# Kasli-SOC_bank13.net
KiCad netlist of a schematic drawn in Altium Designer
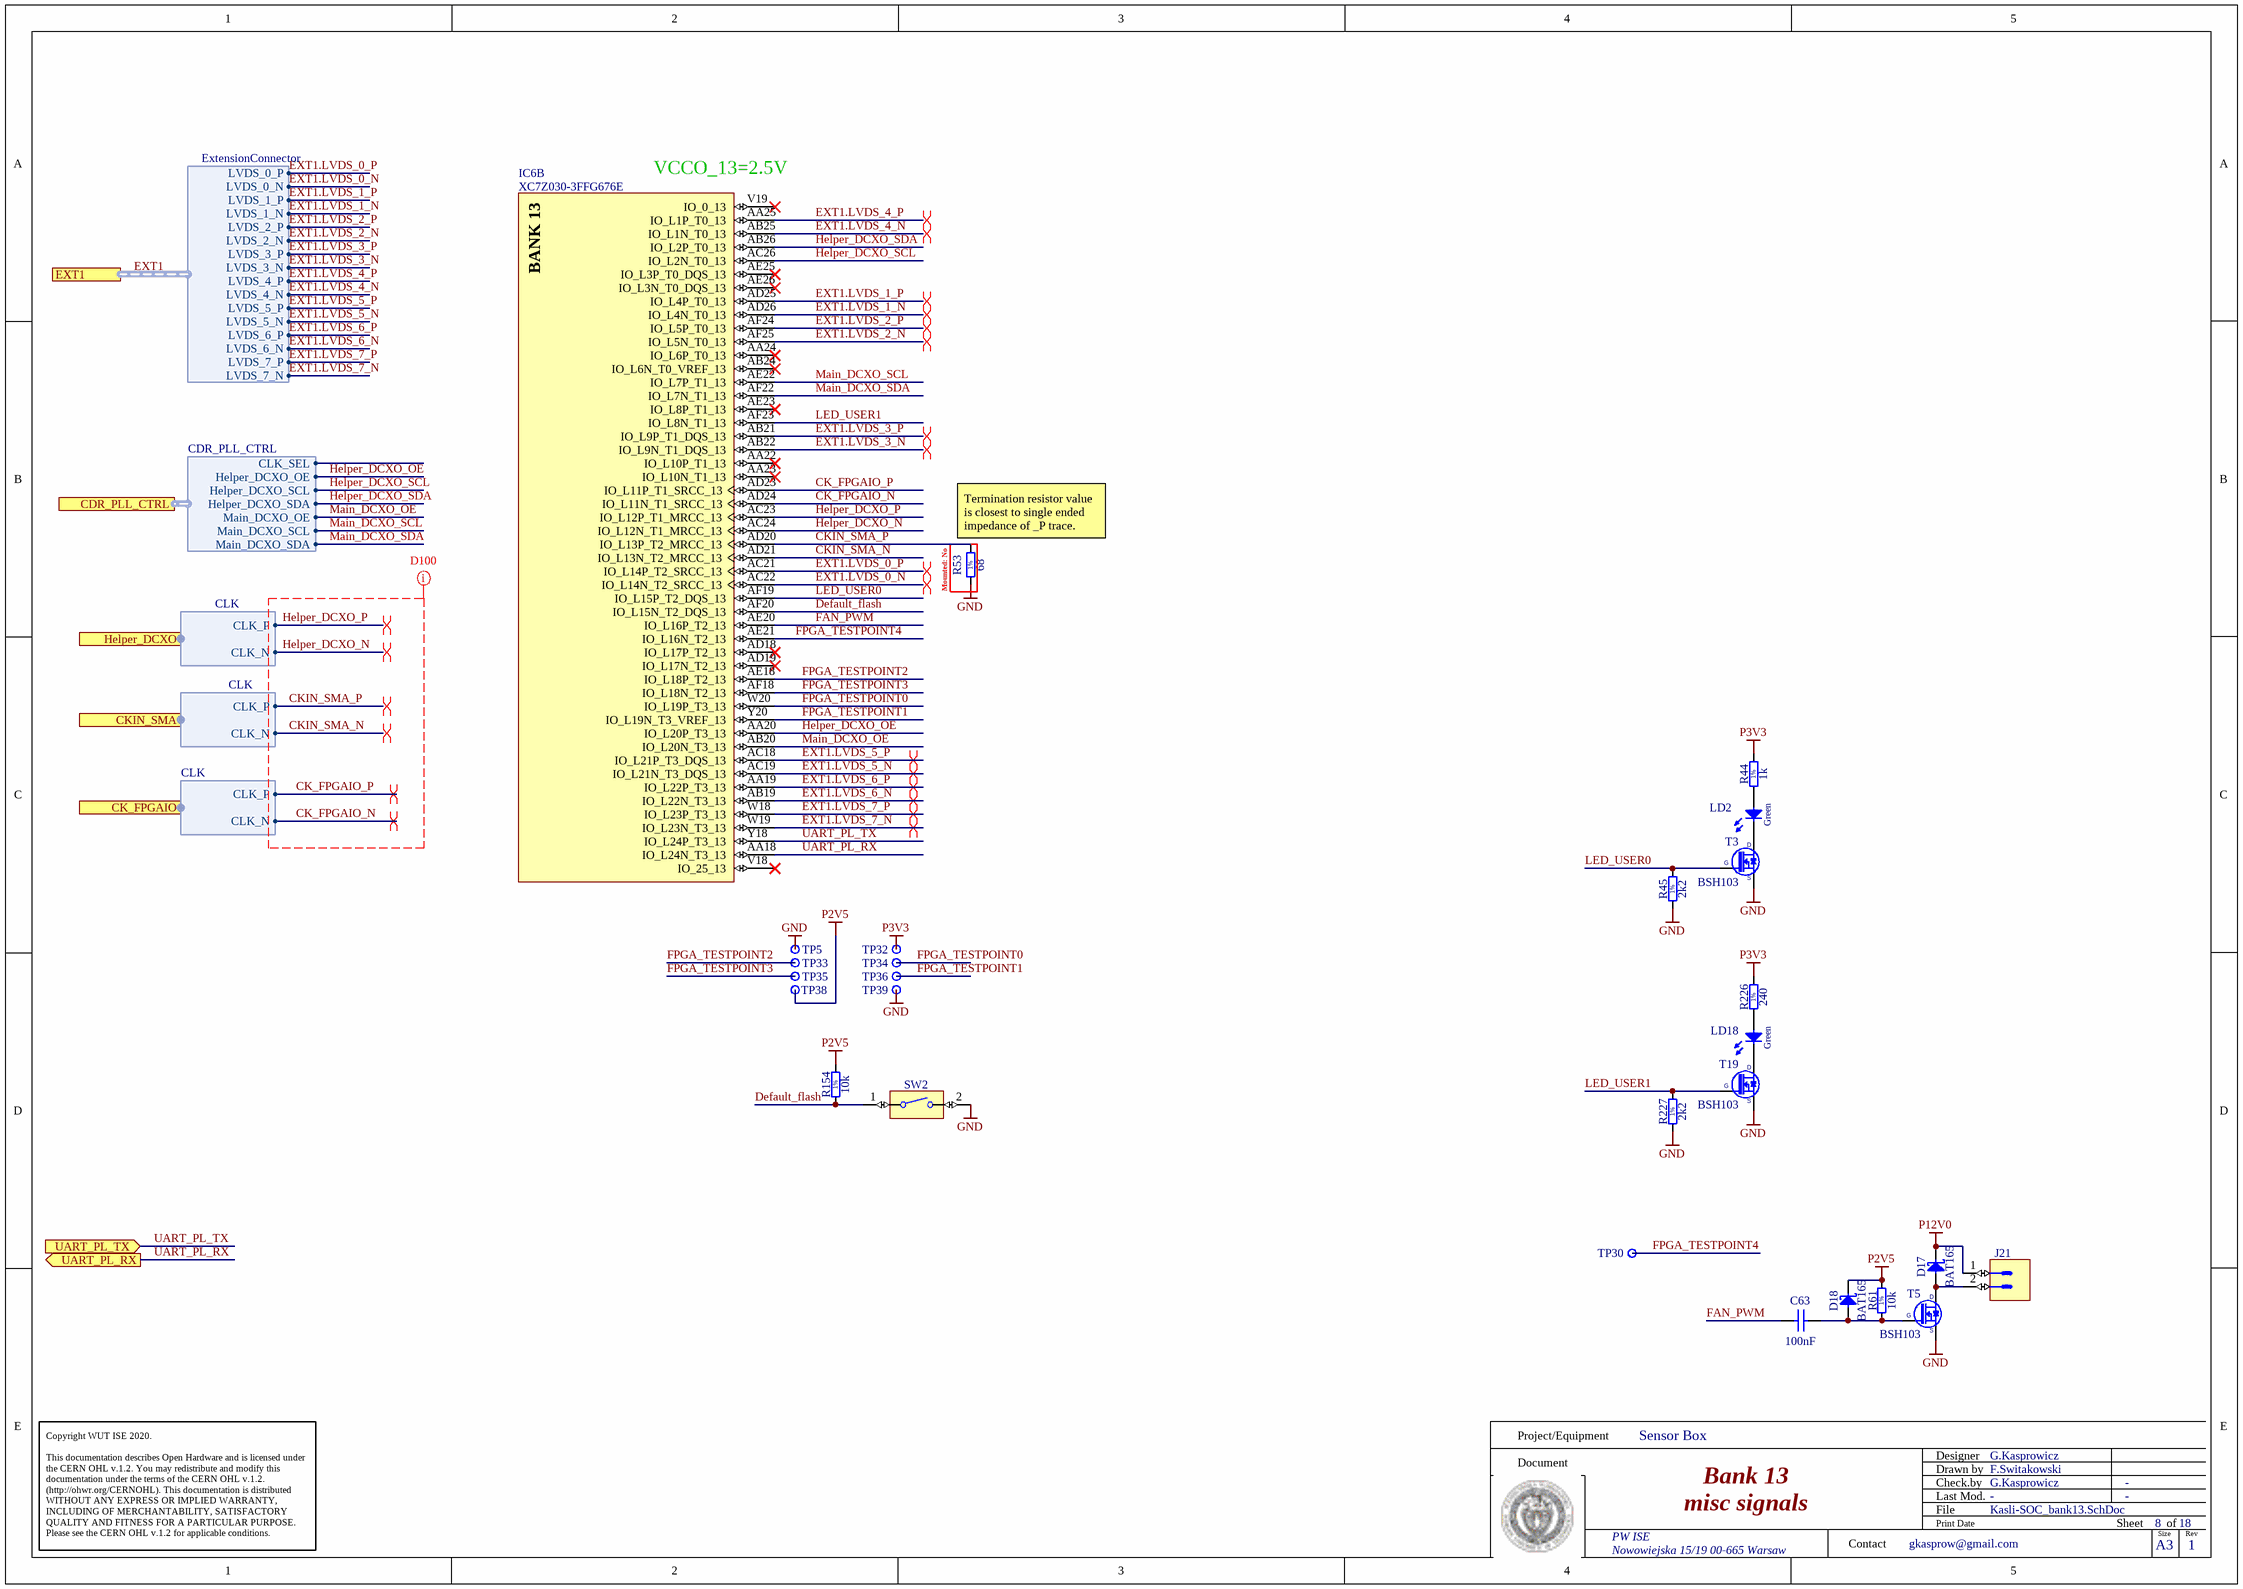
[diagram p0: Kasli-SOC_bank13.SchDoc]

(export (version "E")
  (design (tool "Eeschema 10.0.6"))
  (components
    (comp (ref "C63")
      (value "100nF")
      (footprint "CAPC0603X33N")
      (description "Non-polarised capacitor")
      (fields
        (field (name "PART NUMBER") "CC0201_100NF_6.3V_10%_X5R")
        (field (name "VOLTAGE") "6.3V")
        (field (name "AUTHOR") "CERN DEM JLC")
      )
      (libsource (lib "Capacitors") (part "Capacitor - non polarized"))
    )
    (comp (ref "D17")
      (value "BAT165")
      (footprint "SOD2512X110N")
      (description "Schottky Diode")
      (fields
        (field (name "VOLTAGE") "40V")
        (field (name "POWER") "750mA")
        (field (name "AUTHOR") "CERN DEM JLC")
      )
      (libsource (lib "ICs And Semiconductors") (part "Diode Schottky"))
    )
    (comp (ref "D18")
      (value "BAT165")
      (footprint "SOD2512X110N")
      (description "Schottky Diode")
      (fields
        (field (name "VOLTAGE") "40V")
        (field (name "POWER") "750mA")
        (field (name "AUTHOR") "CERN DEM JLC")
      )
      (libsource (lib "ICs And Semiconductors") (part "Diode Schottky"))
    )
    (comp (ref "IC6")
      (value "XC7Z030-3FFG676E")
      (footprint "BGA676C100P26X26_2700X2700X324")
      (fields (field (name "MANUFACTURER") "XILINX") (field (name "AUTHOR") "CERN DEM JLC"))
      (libsource (lib "ICs And Semiconductors") (part "XC7Z030-2FFG676I"))
    )
    (comp (ref "J21")
      (value "KK®")
      (footprint "MOLEX_22-27-2021")
      (description "Connector 2 Male")
      (fields
        (field (name "PART NUMBER") "MOLEX_22-27-2021")
        (field (name "MANUFACTURER") "MOLEX")
        (field (name "AUTHOR") "CERN DEM JLC")
      )
      (libsource (lib "Connectors") (part "Connector 2 Male"))
    )
    (comp (ref "LD2")
      (value "Green")
      (footprint "LED_KINGBRIGHT_KPH-1608CGCK")
      (description "LED Green 1C 2A")
      (fields
        (field (name "MANUFACTURER PART NUMBER") "KPH-1608CGCK")
        (field (name "PART NUMBER") "LED_KINGBRIGHT_KPH-1608CGCK")
        (field (name "AUTHOR") "CERN DEM JLC")
      )
      (libsource (lib "ICs And Semiconductors") (part "LED Green 1C 2A"))
    )
    (comp (ref "LD18")
      (value "Green")
      (footprint "LED_AVAGO_HSME-C120")
      (description "LED Green 1C 2A")
      (fields
        (field (name "MANUFACTURER PART NUMBER") "HSME-C120")
        (field (name "PART NUMBER") "LED_AVAGO_HSME-C120")
        (field (name "AUTHOR") "CERN DEM JMW")
      )
      (libsource (lib "ICs And Semiconductors") (part "LED Green 1C 2A"))
    )
    (comp (ref "R44")
      (value "1k")
      (footprint "RESC1005X40N")
      (description "Resistor - 1%")
      (fields
        (field (name "PART NUMBER") "R0402_1K_1%_0.0625W_100PPM")
        (field (name "POWER") "0.0625W")
        (field (name "AUTHOR") "CERN DEM JLC")
      )
      (libsource (lib "Resistors") (part "Resistor - 1%"))
    )
    (comp (ref "R45")
      (value "2k2")
      (footprint "RESC1005X40N")
      (description "Resistor - 1%")
      (fields
        (field (name "PART NUMBER") "R0402_2K2_1%_0.0625W_100PPM")
        (field (name "POWER") "0.0625W")
        (field (name "AUTHOR") "CERN DEM JLC")
      )
      (libsource (lib "Resistors") (part "Resistor - 1%"))
    )
    (comp (ref "R53")
      (value "68")
      (footprint "RESC1005X40N")
      (description "Resistor - 1%")
      (fields
        (field (name "PART NUMBER") "R0402_68R_1%_0.0625W_100PPM")
        (field (name "POWER") "0.0625W")
        (field (name "AUTHOR") "CERN DEM JLC")
      )
      (libsource (lib "Resistors") (part "Resistor - 1%"))
    )
    (comp (ref "R61")
      (value "10k")
      (footprint "RESC1005X40N")
      (description "Resistor - 1%")
      (fields
        (field (name "PART NUMBER") "R0402_10K_1%_0.0625W_100PPM")
        (field (name "POWER") "0.0625W")
        (field (name "AUTHOR") "CERN DEM JLC")
      )
      (libsource (lib "Resistors") (part "Resistor - 1%"))
    )
    (comp (ref "R154")
      (value "10k")
      (footprint "RESC1005X40N")
      (description "Resistor - 1%")
      (fields
        (field (name "PART NUMBER") "R0402_10K_1%_0.0625W_100PPM")
        (field (name "POWER") "0.0625W")
        (field (name "AUTHOR") "CERN DEM JLC")
      )
      (libsource (lib "Resistors") (part "Resistor - 1%"))
    )
    (comp (ref "R226")
      (value "240")
      (footprint "RESC1005X40N")
      (description "Resistor - 1%")
      (fields
        (field (name "PART NUMBER") "R0402_240R_1%_0.0625W_100PPM")
        (field (name "POWER") "0.0625W")
        (field (name "AUTHOR") "CERN DEM JLC")
      )
      (libsource (lib "Resistors") (part "Resistor - 1%"))
    )
    (comp (ref "R227")
      (value "2k2")
      (footprint "RESC1005X40N")
      (description "Resistor - 1%")
      (fields
        (field (name "PART NUMBER") "R0402_2K2_1%_0.0625W_100PPM")
        (field (name "POWER") "0.0625W")
        (field (name "AUTHOR") "CERN DEM JLC")
      )
      (libsource (lib "Resistors") (part "Resistor - 1%"))
    )
    (comp (ref "SW2")
      (value "Switch")
      (footprint "SW_OMRON_B3U-3000PM")
      (description "1 Ways SPST DIP Switch")
      (fields
        (field (name "PART NUMBER") "SW_OMRON_B3U-3000PM")
        (field (name "MANUFACTURER") "OMRON")
        (field (name "AUTHOR") "CERN DEM HF")
      )
      (libsource (lib "Eletro-mechanical") (part "SW 1x SPST DIP Switch"))
    )
    (comp (ref "T3")
      (value "BSH103")
      (footprint "SOT95P230X110-3N")
      (description "N-CHANNEL MOSFET WITH DIODE")
      (fields (field (name "MANUFACTURER") "NEXPERIA") (field (name "AUTHOR") "CERN DEM JLC"))
      (libsource (lib "ICs And Semiconductors") (part "N-MOSFET-D 1G 2S 3D"))
    )
    (comp (ref "T5")
      (value "BSH103")
      (footprint "SOT95P230X110-3N")
      (description "N-CHANNEL MOSFET WITH DIODE")
      (fields (field (name "MANUFACTURER") "NEXPERIA") (field (name "AUTHOR") "CERN DEM JLC"))
      (libsource (lib "ICs And Semiconductors") (part "N-MOSFET-D 1G 2S 3D"))
    )
    (comp (ref "T19")
      (value "BSH103")
      (footprint "SOT95P230X110-3N")
      (description "N-CHANNEL MOSFET WITH DIODE")
      (fields (field (name "MANUFACTURER") "NEXPERIA") (field (name "AUTHOR") "CERN DEM JLC"))
      (libsource (lib "ICs And Semiconductors") (part "N-MOSFET-D 1G 2S 3D"))
    )
    (comp (ref "TP5")
      (value "Plated Hole")
      (footprint "c170h100")
      (description "Single Terminal Socket")
      (fields (field (name "PART NUMBER") "PLATED_HOLE1.0_PAD1.7") (field (name "AUTHOR") "CERN DEM JLC"))
      (libsource (lib "Eletro-mechanical") (part "Single Terminal Socket"))
    )
    (comp (ref "TP30")
      (value "Test Point")
      (footprint "TPS127")
      (fields (field (name "PART NUMBER") "SMD_PAD_1.27X1.27MM") (field (name "AUTHOR") "CERN DEM JLC"))
      (libsource (lib "Eletro-mechanical") (part "Test Point"))
    )
    (comp (ref "TP32")
      (value "Plated Hole")
      (footprint "c170h100")
      (description "Single Terminal Socket")
      (fields (field (name "PART NUMBER") "PLATED_HOLE1.0_PAD1.7") (field (name "AUTHOR") "CERN DEM JLC"))
      (libsource (lib "Eletro-mechanical") (part "Single Terminal Socket"))
    )
    (comp (ref "TP33")
      (value "Plated Hole")
      (footprint "c170h100")
      (description "Single Terminal Socket")
      (fields (field (name "PART NUMBER") "PLATED_HOLE1.0_PAD1.7") (field (name "AUTHOR") "CERN DEM JLC"))
      (libsource (lib "Eletro-mechanical") (part "Single Terminal Socket"))
    )
    (comp (ref "TP34")
      (value "Plated Hole")
      (footprint "c170h100")
      (description "Single Terminal Socket")
      (fields (field (name "PART NUMBER") "PLATED_HOLE1.0_PAD1.7") (field (name "AUTHOR") "CERN DEM JLC"))
      (libsource (lib "Eletro-mechanical") (part "Single Terminal Socket"))
    )
    (comp (ref "TP35")
      (value "Plated Hole")
      (footprint "c170h100")
      (description "Single Terminal Socket")
      (fields (field (name "PART NUMBER") "PLATED_HOLE1.0_PAD1.7") (field (name "AUTHOR") "CERN DEM JLC"))
      (libsource (lib "Eletro-mechanical") (part "Single Terminal Socket"))
    )
    (comp (ref "TP36")
      (value "Plated Hole")
      (footprint "c170h100")
      (description "Single Terminal Socket")
      (fields (field (name "PART NUMBER") "PLATED_HOLE1.0_PAD1.7") (field (name "AUTHOR") "CERN DEM JLC"))
      (libsource (lib "Eletro-mechanical") (part "Single Terminal Socket"))
    )
    (comp (ref "TP38")
      (value "Plated Hole")
      (footprint "c170h100")
      (description "Single Terminal Socket")
      (fields (field (name "PART NUMBER") "PLATED_HOLE1.0_PAD1.7") (field (name "AUTHOR") "CERN DEM JLC"))
      (libsource (lib "Eletro-mechanical") (part "Single Terminal Socket"))
    )
    (comp (ref "TP39")
      (value "Plated Hole")
      (footprint "c170h100")
      (description "Single Terminal Socket")
      (fields (field (name "PART NUMBER") "PLATED_HOLE1.0_PAD1.7") (field (name "AUTHOR") "CERN DEM JLC"))
      (libsource (lib "Eletro-mechanical") (part "Single Terminal Socket"))
    )
  )
  (nets
    (net (code "4") (name "/CKIN_SMA_N") (class "Default")
      (node (ref "IC6") (pin "AD21") (pinfunction "IO_L13N_T2_MRCC_13_AD21") (pintype "bidirectional"))
    )
    (net (code "5") (name "/CKIN_SMA_P") (class "Default")
      (node (ref "IC6") (pin "AD20") (pinfunction "IO_L13P_T2_MRCC_13_AD20") (pintype "bidirectional"))
      (node (ref "R53") (pin "2") (pinfunction "2_2") (pintype "passive"))
    )
    (net (code "6") (name "/CK_FPGAIO_N") (class "Default")
      (node (ref "IC6") (pin "AD24") (pinfunction "IO_L11N_T1_SRCC_13_AD24") (pintype "bidirectional"))
    )
    (net (code "7") (name "/CK_FPGAIO_P") (class "Default")
      (node (ref "IC6") (pin "AD23") (pinfunction "IO_L11P_T1_SRCC_13_AD23") (pintype "bidirectional"))
    )
    (net (code "8") (name "/Default_flash") (class "Default")
      (node (ref "IC6") (pin "AF20") (pinfunction "IO_L15N_T2_DQS_13_AF20") (pintype "bidirectional"))
      (node (ref "R154") (pin "1") (pinfunction "1_1") (pintype "passive"))
      (node (ref "SW2") (pin "1") (pinfunction "1_1") (pintype "bidirectional"))
    )
    (net (code "9") (name "/EXT1.LVDS_0_N") (class "Default")
      (node (ref "IC6") (pin "AC22") (pinfunction "IO_L14N_T2_SRCC_13_AC22") (pintype "bidirectional"))
    )
    (net (code "10") (name "/EXT1.LVDS_0_P") (class "Default")
      (node (ref "IC6") (pin "AC21") (pinfunction "IO_L14P_T2_SRCC_13_AC21") (pintype "bidirectional"))
    )
    (net (code "11") (name "/EXT1.LVDS_1_N") (class "Default")
      (node (ref "IC6") (pin "AD26") (pinfunction "IO_L4N_T0_13_AD26") (pintype "bidirectional"))
    )
    (net (code "12") (name "/EXT1.LVDS_1_P") (class "Default")
      (node (ref "IC6") (pin "AD25") (pinfunction "IO_L4P_T0_13_AD25") (pintype "bidirectional"))
    )
    (net (code "13") (name "/EXT1.LVDS_2_N") (class "Default")
      (node (ref "IC6") (pin "AF25") (pinfunction "IO_L5N_T0_13_AF25") (pintype "bidirectional"))
    )
    (net (code "14") (name "/EXT1.LVDS_2_P") (class "Default")
      (node (ref "IC6") (pin "AF24") (pinfunction "IO_L5P_T0_13_AF24") (pintype "bidirectional"))
    )
    (net (code "15") (name "/EXT1.LVDS_3_N") (class "Default")
      (node (ref "IC6") (pin "AB22") (pinfunction "IO_L9N_T1_DQS_13_AB22") (pintype "bidirectional"))
    )
    (net (code "16") (name "/EXT1.LVDS_3_P") (class "Default")
      (node (ref "IC6") (pin "AB21") (pinfunction "IO_L9P_T1_DQS_13_AB21") (pintype "bidirectional"))
    )
    (net (code "17") (name "/EXT1.LVDS_4_N") (class "Default")
      (node (ref "IC6") (pin "AB25") (pinfunction "IO_L1N_T0_13_AB25") (pintype "bidirectional"))
    )
    (net (code "18") (name "/EXT1.LVDS_4_P") (class "Default")
      (node (ref "IC6") (pin "AA25") (pinfunction "IO_L1P_T0_13_AA25") (pintype "bidirectional"))
    )
    (net (code "19") (name "/EXT1.LVDS_5_N") (class "Default")
      (node (ref "IC6") (pin "AC19") (pinfunction "IO_L21N_T3_DQS_13_AC19") (pintype "bidirectional"))
    )
    (net (code "20") (name "/EXT1.LVDS_5_P") (class "Default")
      (node (ref "IC6") (pin "AC18") (pinfunction "IO_L21P_T3_DQS_13_AC18") (pintype "bidirectional"))
    )
    (net (code "21") (name "/EXT1.LVDS_6_N") (class "Default")
      (node (ref "IC6") (pin "AB19") (pinfunction "IO_L22N_T3_13_AB19") (pintype "bidirectional"))
    )
    (net (code "22") (name "/EXT1.LVDS_6_P") (class "Default")
      (node (ref "IC6") (pin "AA19") (pinfunction "IO_L22P_T3_13_AA19") (pintype "bidirectional"))
    )
    (net (code "23") (name "/EXT1.LVDS_7_N") (class "Default")
      (node (ref "IC6") (pin "W19") (pinfunction "IO_L23N_T3_13_W19") (pintype "bidirectional"))
    )
    (net (code "24") (name "/EXT1.LVDS_7_P") (class "Default")
      (node (ref "IC6") (pin "W18") (pinfunction "IO_L23P_T3_13_W18") (pintype "bidirectional"))
    )
    (net (code "26") (name "/FAN_PWM") (class "Default")
      (node (ref "C63") (pin "2") (pinfunction "2_2") (pintype "passive"))
      (node (ref "IC6") (pin "AE20") (pinfunction "IO_L16P_T2_13_AE20") (pintype "bidirectional"))
    )
    (net (code "27") (name "/FPGA_TESTPOINT0") (class "Default")
      (node (ref "IC6") (pin "W20") (pinfunction "IO_L19P_T3_13_W20") (pintype "bidirectional"))
      (node (ref "TP34") (pin "1") (pinfunction "1_1") (pintype "bidirectional"))
    )
    (net (code "28") (name "/FPGA_TESTPOINT1") (class "Default")
      (node (ref "IC6") (pin "Y20") (pinfunction "IO_L19N_T3_VREF_13_Y20") (pintype "bidirectional"))
      (node (ref "TP36") (pin "1") (pinfunction "1_1") (pintype "bidirectional"))
    )
    (net (code "29") (name "/FPGA_TESTPOINT2") (class "Default")
      (node (ref "IC6") (pin "AE18") (pinfunction "IO_L18P_T2_13_AE18") (pintype "bidirectional"))
      (node (ref "TP33") (pin "1") (pinfunction "1_1") (pintype "bidirectional"))
    )
    (net (code "30") (name "/FPGA_TESTPOINT3") (class "Default")
      (node (ref "IC6") (pin "AF18") (pinfunction "IO_L18N_T2_13_AF18") (pintype "bidirectional"))
      (node (ref "TP35") (pin "1") (pinfunction "1_1") (pintype "bidirectional"))
    )
    (net (code "31") (name "/FPGA_TESTPOINT4") (class "Default")
      (node (ref "IC6") (pin "AE21") (pinfunction "IO_L16N_T2_13_AE21") (pintype "bidirectional"))
      (node (ref "TP30") (pin "1") (pinfunction "1_1") (pintype "bidirectional"))
    )
    (net (code "32") (name "/Helper_DCXO_N") (class "Default")
      (node (ref "IC6") (pin "AC24") (pinfunction "IO_L12N_T1_MRCC_13_AC24") (pintype "bidirectional"))
    )
    (net (code "33") (name "/Helper_DCXO_OE") (class "Default")
      (node (ref "IC6") (pin "AA20") (pinfunction "IO_L20P_T3_13_AA20") (pintype "bidirectional"))
    )
    (net (code "34") (name "/Helper_DCXO_P") (class "Default")
      (node (ref "IC6") (pin "AC23") (pinfunction "IO_L12P_T1_MRCC_13_AC23") (pintype "bidirectional"))
    )
    (net (code "35") (name "/Helper_DCXO_SCL") (class "Default")
      (node (ref "IC6") (pin "AC26") (pinfunction "IO_L2N_T0_13_AC26") (pintype "bidirectional"))
    )
    (net (code "36") (name "/Helper_DCXO_SDA") (class "Default")
      (node (ref "IC6") (pin "AB26") (pinfunction "IO_L2P_T0_13_AB26") (pintype "bidirectional"))
    )
    (net (code "37") (name "/LED_USER0") (class "Default")
      (node (ref "IC6") (pin "AF19") (pinfunction "IO_L15P_T2_DQS_13_AF19") (pintype "bidirectional"))
      (node (ref "R45") (pin "2") (pinfunction "2_2") (pintype "passive"))
      (node (ref "T3") (pin "1") (pinfunction "G_1") (pintype "passive"))
    )
    (net (code "38") (name "/LED_USER1") (class "Default")
      (node (ref "IC6") (pin "AF23") (pinfunction "IO_L8N_T1_13_AF23") (pintype "bidirectional"))
      (node (ref "R227") (pin "2") (pinfunction "2_2") (pintype "passive"))
      (node (ref "T19") (pin "1") (pinfunction "G_1") (pintype "passive"))
    )
    (net (code "39") (name "/Main_DCXO_OE") (class "Default")
      (node (ref "IC6") (pin "AB20") (pinfunction "IO_L20N_T3_13_AB20") (pintype "bidirectional"))
    )
    (net (code "40") (name "/Main_DCXO_SCL") (class "Default")
      (node (ref "IC6") (pin "AE22") (pinfunction "IO_L7P_T1_13_AE22") (pintype "bidirectional"))
    )
    (net (code "41") (name "/Main_DCXO_SDA") (class "Default")
      (node (ref "IC6") (pin "AF22") (pinfunction "IO_L7N_T1_13_AF22") (pintype "bidirectional"))
    )
    (net (code "42") (name "/UART_PL_RX") (class "Default")
      (node (ref "IC6") (pin "AA18") (pinfunction "IO_L24N_T3_13_AA18") (pintype "bidirectional"))
    )
    (net (code "43") (name "/UART_PL_TX") (class "Default")
      (node (ref "IC6") (pin "Y18") (pinfunction "IO_L24P_T3_13_Y18") (pintype "bidirectional"))
    )
    (net (code "46") (name "GND") (class "Default")
      (node (ref "R227") (pin "1") (pinfunction "1_1") (pintype "passive"))
      (node (ref "R45") (pin "1") (pinfunction "1_1") (pintype "passive"))
      (node (ref "R53") (pin "1") (pinfunction "1_1") (pintype "passive"))
      (node (ref "SW2") (pin "2") (pinfunction "2_2") (pintype "bidirectional"))
      (node (ref "T19") (pin "2") (pinfunction "S_2") (pintype "passive"))
      (node (ref "T3") (pin "2") (pinfunction "S_2") (pintype "passive"))
      (node (ref "T5") (pin "2") (pinfunction "S_2") (pintype "passive"))
      (node (ref "TP39") (pin "1") (pinfunction "1_1") (pintype "bidirectional"))
      (node (ref "TP5") (pin "1") (pinfunction "1_1") (pintype "bidirectional"))
    )
    (net (code "47") (name "Net-(D17-A)") (class "Default")
      (node (ref "D17") (pin "2") (pinfunction "A_2") (pintype "passive"))
      (node (ref "J21") (pin "2") (pinfunction "2_2") (pintype "bidirectional"))
      (node (ref "T5") (pin "3") (pinfunction "D_3") (pintype "passive"))
    )
    (net (code "48") (name "Net-(D18-A)") (class "Default")
      (node (ref "C63") (pin "1") (pinfunction "1_1") (pintype "passive"))
      (node (ref "D18") (pin "2") (pinfunction "A_2") (pintype "passive"))
      (node (ref "R61") (pin "1") (pinfunction "1_1") (pintype "passive"))
      (node (ref "T5") (pin "1") (pinfunction "G_1") (pintype "passive"))
    )
    (net (code "49") (name "Net-(LD2-A)") (class "Default")
      (node (ref "LD2") (pin "2") (pinfunction "A_2") (pintype "passive"))
      (node (ref "R44") (pin "1") (pinfunction "1_1") (pintype "passive"))
    )
    (net (code "50") (name "Net-(LD2-C)") (class "Default")
      (node (ref "LD2") (pin "1") (pinfunction "C_1") (pintype "passive"))
      (node (ref "T3") (pin "3") (pinfunction "D_3") (pintype "passive"))
    )
    (net (code "51") (name "Net-(LD18-A)") (class "Default")
      (node (ref "LD18") (pin "2") (pinfunction "A_2") (pintype "passive"))
      (node (ref "R226") (pin "1") (pinfunction "1_1") (pintype "passive"))
    )
    (net (code "52") (name "Net-(LD18-C)") (class "Default")
      (node (ref "LD18") (pin "1") (pinfunction "C_1") (pintype "passive"))
      (node (ref "T19") (pin "3") (pinfunction "D_3") (pintype "passive"))
    )
    (net (code "53") (name "P2V5") (class "Default")
      (node (ref "D18") (pin "1") (pinfunction "C_1") (pintype "passive"))
      (node (ref "R154") (pin "2") (pinfunction "2_2") (pintype "passive"))
      (node (ref "R61") (pin "2") (pinfunction "2_2") (pintype "passive"))
      (node (ref "TP38") (pin "1") (pinfunction "1_1") (pintype "bidirectional"))
    )
    (net (code "54") (name "P3V3") (class "Default")
      (node (ref "R226") (pin "2") (pinfunction "2_2") (pintype "passive"))
      (node (ref "R44") (pin "2") (pinfunction "2_2") (pintype "passive"))
      (node (ref "TP32") (pin "1") (pinfunction "1_1") (pintype "bidirectional"))
    )
    (net (code "55") (name "P12V0") (class "Default")
      (node (ref "D17") (pin "1") (pinfunction "C_1") (pintype "passive"))
      (node (ref "J21") (pin "1") (pinfunction "1_1") (pintype "bidirectional"))
    )
    (net (code "56") (name "unconnected-(IC6B-IO_0_13-PadV19)") (class "Default")
      (node (ref "IC6") (pin "V19") (pinfunction "IO_0_13_V19") (pintype "bidirectional+no_connect"))
    )
    (net (code "57") (name "unconnected-(IC6B-IO_25_13-PadV18)") (class "Default")
      (node (ref "IC6") (pin "V18") (pinfunction "IO_25_13_V18") (pintype "bidirectional+no_connect"))
    )
    (net (code "58") (name "unconnected-(IC6B-IO_L3N_T0_DQS_13-PadAE26)") (class "Default")
      (node (ref "IC6") (pin "AE26") (pinfunction "IO_L3N_T0_DQS_13_AE26") (pintype "bidirectional+no_connect"))
    )
    (net (code "59") (name "unconnected-(IC6B-IO_L3P_T0_DQS_13-PadAE25)") (class "Default")
      (node (ref "IC6") (pin "AE25") (pinfunction "IO_L3P_T0_DQS_13_AE25") (pintype "bidirectional+no_connect"))
    )
    (net (code "60") (name "unconnected-(IC6B-IO_L6N_T0_VREF_13-PadAB24)") (class "Default")
      (node (ref "IC6") (pin "AB24") (pinfunction "IO_L6N_T0_VREF_13_AB24") (pintype "bidirectional+no_connect"))
    )
    (net (code "61") (name "unconnected-(IC6B-IO_L6P_T0_13-PadAA24)") (class "Default")
      (node (ref "IC6") (pin "AA24") (pinfunction "IO_L6P_T0_13_AA24") (pintype "bidirectional+no_connect"))
    )
    (net (code "62") (name "unconnected-(IC6B-IO_L8P_T1_13-PadAE23)") (class "Default")
      (node (ref "IC6") (pin "AE23") (pinfunction "IO_L8P_T1_13_AE23") (pintype "bidirectional+no_connect"))
    )
    (net (code "63") (name "unconnected-(IC6B-IO_L10N_T1_13-PadAA23)") (class "Default")
      (node (ref "IC6") (pin "AA23") (pinfunction "IO_L10N_T1_13_AA23") (pintype "bidirectional+no_connect"))
    )
    (net (code "64") (name "unconnected-(IC6B-IO_L10P_T1_13-PadAA22)") (class "Default")
      (node (ref "IC6") (pin "AA22") (pinfunction "IO_L10P_T1_13_AA22") (pintype "bidirectional+no_connect"))
    )
    (net (code "65") (name "unconnected-(IC6B-IO_L17N_T2_13-PadAD19)") (class "Default")
      (node (ref "IC6") (pin "AD19") (pinfunction "IO_L17N_T2_13_AD19") (pintype "bidirectional+no_connect"))
    )
    (net (code "66") (name "unconnected-(IC6B-IO_L17P_T2_13-PadAD18)") (class "Default")
      (node (ref "IC6") (pin "AD18") (pinfunction "IO_L17P_T2_13_AD18") (pintype "bidirectional+no_connect"))
    )
  )
)
